# LB-word-diffI2C.net
KiCad netlist of a schematic drawn in Altium Designer
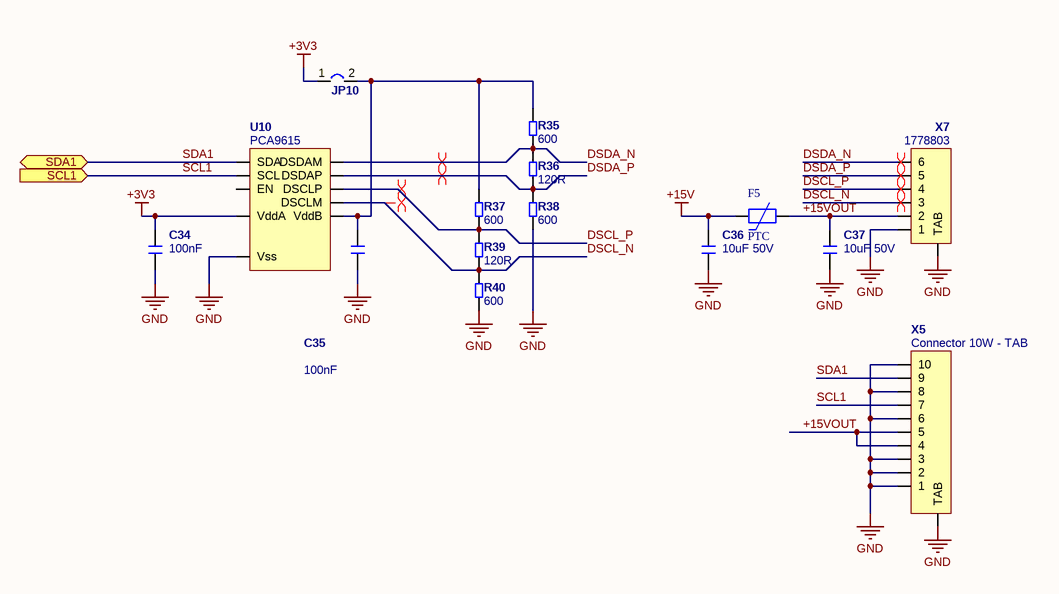
[diagram p0: LB-word-diffI2C.SchDoc]

(export (version "E")
  (design (tool "Eeschema 10.0.6"))
  (components
    (comp (ref "C34")
      (value "100nF")
      (footprint "C0603_N")
      (description "Capacitor MLCC")
      (fields
        (field (name "MANUFACTURER") "Yageo")
        (field (name "MANUFACTURER PART NUMBER") "CC0603KRX7R9BB104")
      )
      (libsource (lib "wes") (part "Capacitor"))
    )
    (comp (ref "C35")
      (value "100nF")
      (footprint "C0603_N")
      (description "Capacitor MLCC")
      (fields
        (field (name "MANUFACTURER") "Yageo")
        (field (name "MANUFACTURER PART NUMBER") "CC0603KRX7R9BB104")
      )
      (libsource (lib "wes") (part "Capacitor"))
    )
    (comp (ref "C36")
      (value "10uF 50V")
      (footprint "C1210_N")
      (description "Capacitor MLCC")
      (fields
        (field (name "MANUFACTURER") "Yageo")
        (field (name "MANUFACTURER PART NUMBER") "CC0603KRX7R9BB104")
      )
      (libsource (lib "wes") (part "Capacitor"))
    )
    (comp (ref "C37")
      (value "10uF 50V")
      (footprint "C1210_N")
      (description "Capacitor MLCC")
      (fields
        (field (name "MANUFACTURER") "Yageo")
        (field (name "MANUFACTURER PART NUMBER") "CC0603KRX7R9BB104")
      )
      (libsource (lib "wes") (part "Capacitor"))
    )
    (comp (ref "F5")
      (value "PTC")
      (footprint "1812")
      (description "PTC, Resettable Fuse")
      (libsource (lib "wes") (part "PTC"))
    )
    (comp (ref "JP10")
      (value "Jumper 2W")
      (footprint "Jumper SMD 2W NO")
      (libsource (lib "wes") (part "Jumper 2W"))
    )
    (comp (ref "R35")
      (value "600")
      (footprint "R0603")
      (fields (field (name "PUBLISHER") "Altium Limited"))
      (libsource (lib "wes") (part "Resistor"))
    )
    (comp (ref "R36")
      (value "120R")
      (footprint "R0603")
      (fields (field (name "PUBLISHER") "Altium Limited"))
      (libsource (lib "wes") (part "Resistor"))
    )
    (comp (ref "R37")
      (value "600")
      (footprint "R0603")
      (fields (field (name "PUBLISHER") "Altium Limited"))
      (libsource (lib "wes") (part "Resistor"))
    )
    (comp (ref "R38")
      (value "600")
      (footprint "R0603")
      (fields (field (name "PUBLISHER") "Altium Limited"))
      (libsource (lib "wes") (part "Resistor"))
    )
    (comp (ref "R39")
      (value "120R")
      (footprint "R0603")
      (fields (field (name "PUBLISHER") "Altium Limited"))
      (libsource (lib "wes") (part "Resistor"))
    )
    (comp (ref "R40")
      (value "600")
      (footprint "R0603")
      (fields (field (name "PUBLISHER") "Altium Limited"))
      (libsource (lib "wes") (part "Resistor"))
    )
    (comp (ref "U10") (value "PCA9615") (footprint "TSSOP10") (libsource (lib "wes") (part "PCA9615DP")))
    (comp (ref "X5")
      (value "Connector 10W - TAB")
      (footprint "FPC Conn. 10W 1-84953-0")
      (libsource (lib "wes") (part "Connector 10W - TAB"))
    )
    (comp (ref "X7")
      (value "1778803")
      (footprint "PTSM-6W-H-SMD")
      (libsource (lib "wes") (part "Connector 6W - TAB"))
    )
  )
  (nets
    (net (code "1") (name "+3V3") (class "Default")
      (node (ref "C34") (pin "1") (pintype "passive"))
      (node (ref "JP10") (pin "1") (pinfunction "1_1") (pintype "passive"))
      (node (ref "U10") (pin "1") (pinfunction "VddA_1") (pintype "passive"))
    )
    (net (code "2") (name "+15V") (class "Default")
      (node (ref "C36") (pin "1") (pintype "passive"))
      (node (ref "F5") (pin "1") (pinfunction "1_1") (pintype "passive"))
    )
    (net (code "3") (name "/+15VOUT") (class "Default")
      (node (ref "C37") (pin "1") (pintype "passive"))
      (node (ref "F5") (pin "2") (pinfunction "2_2") (pintype "passive"))
      (node (ref "X5") (pin "4") (pinfunction "4_4") (pintype "passive"))
      (node (ref "X5") (pin "5") (pinfunction "5_5") (pintype "passive"))
      (node (ref "X7") (pin "2") (pinfunction "2_2") (pintype "power_in"))
    )
    (net (code "4") (name "/DSCL_N") (class "Default")
      (node (ref "R39") (pin "1") (pinfunction "1_1") (pintype "passive"))
      (node (ref "R40") (pin "2") (pinfunction "2_2") (pintype "passive"))
      (node (ref "U10") (pin "6") (pinfunction "DSCLM_6") (pintype "passive"))
      (node (ref "X7") (pin "3") (pinfunction "3_3") (pintype "power_in"))
    )
    (net (code "5") (name "/DSCL_P") (class "Default")
      (node (ref "R37") (pin "1") (pinfunction "1_1") (pintype "passive"))
      (node (ref "R39") (pin "2") (pinfunction "2_2") (pintype "passive"))
      (node (ref "U10") (pin "7") (pinfunction "DSCLP_7") (pintype "passive"))
      (node (ref "X7") (pin "4") (pinfunction "4_4") (pintype "power_in"))
    )
    (net (code "6") (name "/DSDA_N") (class "Default")
      (node (ref "R35") (pin "1") (pinfunction "1_1") (pintype "passive"))
      (node (ref "R36") (pin "2") (pinfunction "2_2") (pintype "passive"))
      (node (ref "U10") (pin "9") (pinfunction "DSDAM_9") (pintype "passive"))
      (node (ref "X7") (pin "6") (pinfunction "6_6") (pintype "power_in"))
    )
    (net (code "7") (name "/DSDA_P") (class "Default")
      (node (ref "R36") (pin "1") (pinfunction "1_1") (pintype "passive"))
      (node (ref "R38") (pin "2") (pinfunction "2_2") (pintype "passive"))
      (node (ref "U10") (pin "8") (pinfunction "DSDAP_8") (pintype "passive"))
      (node (ref "X7") (pin "5") (pinfunction "5_5") (pintype "power_in"))
    )
    (net (code "8") (name "/SCL1") (class "Default")
      (node (ref "U10") (pin "4") (pinfunction "SCL_4") (pintype "passive"))
      (node (ref "X5") (pin "7") (pinfunction "7_7") (pintype "passive"))
    )
    (net (code "9") (name "/SDA1") (class "Default")
      (node (ref "U10") (pin "2") (pinfunction "SDA_2") (pintype "passive"))
      (node (ref "X5") (pin "9") (pinfunction "9_9") (pintype "passive"))
    )
    (net (code "10") (name "GND") (class "Default")
      (node (ref "C34") (pin "2") (pintype "passive"))
      (node (ref "C35") (pin "2") (pintype "passive"))
      (node (ref "C36") (pin "2") (pintype "passive"))
      (node (ref "C37") (pin "2") (pintype "passive"))
      (node (ref "R38") (pin "1") (pinfunction "1_1") (pintype "passive"))
      (node (ref "R40") (pin "1") (pinfunction "1_1") (pintype "passive"))
      (node (ref "U10") (pin "5") (pinfunction "Vss_5") (pintype "passive"))
      (node (ref "X5") (pin "1") (pinfunction "1_1") (pintype "passive"))
      (node (ref "X5") (pin "10") (pinfunction "10_10") (pintype "passive"))
      (node (ref "X5") (pin "2") (pinfunction "2_2") (pintype "passive"))
      (node (ref "X5") (pin "3") (pinfunction "3_3") (pintype "passive"))
      (node (ref "X5") (pin "6") (pinfunction "6_6") (pintype "passive"))
      (node (ref "X5") (pin "8") (pinfunction "8_8") (pintype "passive"))
      (node (ref "X5") (pin "TAB") (pinfunction "TAB_TAB") (pintype "passive"))
      (node (ref "X7") (pin "1") (pinfunction "1_1") (pintype "power_in"))
      (node (ref "X7") (pin "TAB") (pinfunction "TAB_TAB") (pintype "power_in"))
    )
    (net (code "11") (name "Net-(U10-VddB)") (class "Default")
      (node (ref "C35") (pin "1") (pintype "passive"))
      (node (ref "JP10") (pin "2") (pinfunction "2_2") (pintype "passive"))
      (node (ref "R35") (pin "2") (pinfunction "2_2") (pintype "passive"))
      (node (ref "R37") (pin "2") (pinfunction "2_2") (pintype "passive"))
      (node (ref "U10") (pin "10") (pinfunction "VddB_10") (pintype "passive"))
    )
    (net (code "12") (name "unconnected-(U10-EN-Pad3)") (class "Default")
      (node (ref "U10") (pin "3") (pinfunction "EN_3") (pintype "passive"))
    )
  )
)
